# Connectors.net
KiCad netlist of a schematic drawn in Altium Designer
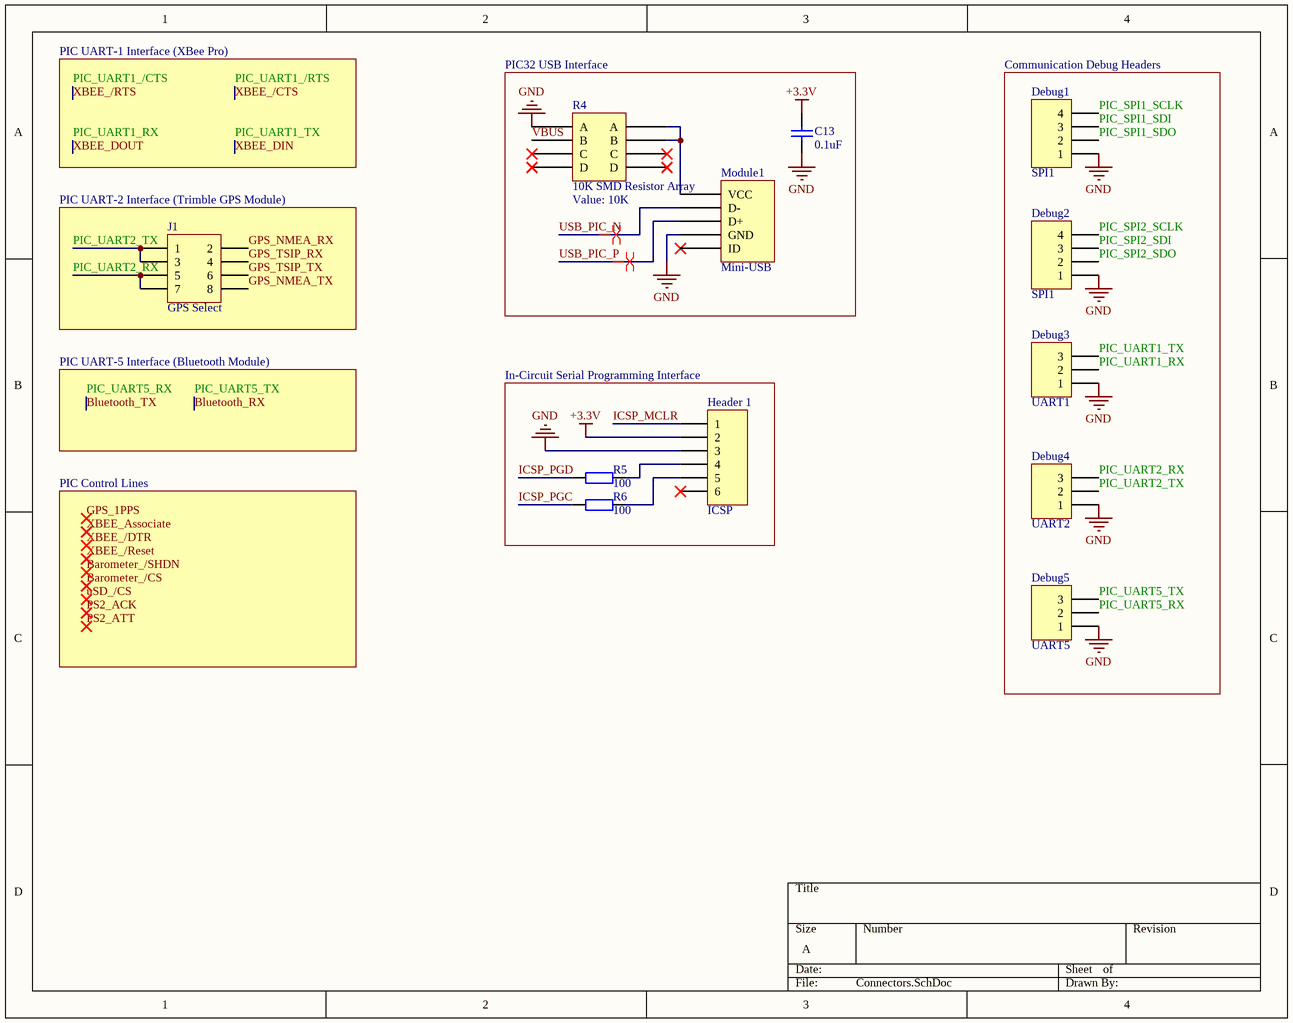
[diagram p0: Connectors.SchDoc]

(export (version "E")
  (design (tool "Eeschema 10.0.6"))
  (components
    (comp (ref "C13")
      (value "0.1uF")
      (footprint "SMD 1206")
      (description "Capacitor")
      (fields (field (name "Comment") "0.1uF SMD 1206"))
      (libsource (lib "Miscellaneous Devices") (part "Cap"))
    )
    (comp (ref "Debug1")
      (value "SPI1")
      (footprint "HDR1X4")
      (description "Header, 4-Pin")
      (fields (field (name "PUBLISHER") "Altium Limited"))
      (libsource (lib "Miscellaneous Connectors") (part "Header 4"))
    )
    (comp (ref "Debug2")
      (value "SPI1")
      (footprint "HDR1X4")
      (description "Header, 4-Pin")
      (fields (field (name "PUBLISHER") "Altium Limited"))
      (libsource (lib "Miscellaneous Connectors") (part "Header 4"))
    )
    (comp (ref "Debug3")
      (value "UART1")
      (footprint "HDR1X3")
      (description "Header, 3-Pin")
      (fields (field (name "PUBLISHER") "Altium Limited"))
      (libsource (lib "Miscellaneous Connectors") (part "Header 3"))
    )
    (comp (ref "Debug4")
      (value "UART2")
      (footprint "HDR1X3")
      (description "Header, 3-Pin")
      (fields (field (name "PUBLISHER") "Altium Limited"))
      (libsource (lib "Miscellaneous Connectors") (part "Header 3"))
    )
    (comp (ref "Debug5")
      (value "UART5")
      (footprint "HDR1X3")
      (description "Header, 3-Pin")
      (fields (field (name "PUBLISHER") "Altium Limited"))
      (libsource (lib "Miscellaneous Connectors") (part "Header 3"))
    )
    (comp (ref "Header 1")
      (value "ICSP")
      (footprint "HDR1X6H")
      (description "Header, 6-Pin")
      (fields (field (name "PUBLISHER") "Altium Limited"))
      (libsource (lib "Miscellaneous Connectors") (part "Header 6"))
    )
    (comp (ref "J1")
      (value "GPS Select")
      (footprint "HDR2X4")
      (description "Header, 4-Pin, Dual row")
      (fields (field (name "PUBLISHER") "Altium Limited"))
      (libsource (lib "Miscellaneous Connectors") (part "Header 4X2"))
    )
    (comp (ref "Module1")
      (value "Mini-USB")
      (footprint "Mini B USB Connector")
      (libsource (lib "Ad-Flier_Parts") (part "Mini USB Connector"))
    )
    (comp (ref "R4")
      (value "10K SMD Resistor Array")
      (footprint "Resistor Array YC164")
      (description "4-Count Resistor Array")
      (fields (field (name "ALTIUM_VALUE") "10K"))
      (libsource (lib "Ad-Flier_Parts") (part "SMD Resistor Array"))
    )
    (comp (ref "R5")
      (value "100")
      (footprint "SMD 0805")
      (description "Resistor")
      (fields (field (name "Comment") "100 SMD 0805"))
      (libsource (lib "Miscellaneous Devices") (part "Res2"))
    )
    (comp (ref "R6")
      (value "100")
      (footprint "SMD 0805")
      (description "Resistor")
      (fields (field (name "Comment") "100 SMD 0805"))
      (libsource (lib "Miscellaneous Devices") (part "Res2"))
    )
  )
  (nets
    (net (code "1") (name "+3.3V") (class "Default")
      (node (ref "C13") (pin "2") (pinfunction "2_2") (pintype "passive"))
      (node (ref "Header 1") (pin "2") (pinfunction "2_2") (pintype "passive"))
    )
    (net (code "4") (name "/Bluetooth_RX") (class "Default")
      (node (ref "Debug5") (pin "3") (pinfunction "3_3") (pintype "passive"))
    )
    (net (code "5") (name "/Bluetooth_TX") (class "Default")
      (node (ref "Debug5") (pin "2") (pinfunction "2_2") (pintype "passive"))
    )
    (net (code "7") (name "/GPS_NMEA_RX") (class "Default")
      (node (ref "J1") (pin "2") (pinfunction "2_2") (pintype "passive"))
    )
    (net (code "8") (name "/GPS_NMEA_TX") (class "Default")
      (node (ref "J1") (pin "8") (pinfunction "8_8") (pintype "passive"))
    )
    (net (code "9") (name "/GPS_TSIP_RX") (class "Default")
      (node (ref "J1") (pin "4") (pinfunction "4_4") (pintype "passive"))
    )
    (net (code "10") (name "/GPS_TSIP_TX") (class "Default")
      (node (ref "J1") (pin "6") (pinfunction "6_6") (pintype "passive"))
    )
    (net (code "11") (name "/ICSP_MCLR") (class "Default")
      (node (ref "Header 1") (pin "1") (pinfunction "1_1") (pintype "passive"))
    )
    (net (code "12") (name "/ICSP_PGC") (class "Default")
      (node (ref "R6") (pin "2") (pinfunction "2_2") (pintype "passive"))
    )
    (net (code "13") (name "/ICSP_PGD") (class "Default")
      (node (ref "R5") (pin "2") (pinfunction "2_2") (pintype "passive"))
    )
    (net (code "14") (name "/PIC_SPI1_SCLK") (class "Default")
      (node (ref "Debug1") (pin "4") (pinfunction "4_4") (pintype "passive"))
    )
    (net (code "15") (name "/PIC_SPI1_SDI") (class "Default")
      (node (ref "Debug1") (pin "3") (pinfunction "3_3") (pintype "passive"))
    )
    (net (code "16") (name "/PIC_SPI1_SDO") (class "Default")
      (node (ref "Debug1") (pin "2") (pinfunction "2_2") (pintype "passive"))
    )
    (net (code "17") (name "/PIC_SPI2_SCLK") (class "Default")
      (node (ref "Debug2") (pin "4") (pinfunction "4_4") (pintype "passive"))
    )
    (net (code "18") (name "/PIC_SPI2_SDI") (class "Default")
      (node (ref "Debug2") (pin "3") (pinfunction "3_3") (pintype "passive"))
    )
    (net (code "19") (name "/PIC_SPI2_SDO") (class "Default")
      (node (ref "Debug2") (pin "2") (pinfunction "2_2") (pintype "passive"))
    )
    (net (code "20") (name "/PIC_UART1_RX") (class "Default")
      (node (ref "Debug3") (pin "2") (pinfunction "2_2") (pintype "passive"))
    )
    (net (code "21") (name "/PIC_UART1_TX") (class "Default")
      (node (ref "Debug3") (pin "3") (pinfunction "3_3") (pintype "passive"))
    )
    (net (code "24") (name "/PIC_UART2_RX") (class "Default")
      (node (ref "Debug4") (pin "3") (pinfunction "3_3") (pintype "passive"))
      (node (ref "J1") (pin "5") (pinfunction "5_5") (pintype "passive"))
      (node (ref "J1") (pin "7") (pinfunction "7_7") (pintype "passive"))
    )
    (net (code "25") (name "/PIC_UART2_TX") (class "Default")
      (node (ref "Debug4") (pin "2") (pinfunction "2_2") (pintype "passive"))
      (node (ref "J1") (pin "1") (pinfunction "1_1") (pintype "passive"))
      (node (ref "J1") (pin "3") (pinfunction "3_3") (pintype "passive"))
    )
    (net (code "28") (name "/USB_PIC_N") (class "Default")
      (node (ref "Module1") (pin "3") (pinfunction "D-_3") (pintype "passive"))
    )
    (net (code "29") (name "/USB_PIC_P") (class "Default")
      (node (ref "Module1") (pin "2") (pinfunction "D+_2") (pintype "passive"))
    )
    (net (code "30") (name "/VBUS") (class "Default")
      (node (ref "R4") (pin "6") (pinfunction "B_6") (pintype "passive"))
    )
    (net (code "35") (name "GND") (class "Default")
      (node (ref "C13") (pin "1") (pinfunction "1_1") (pintype "passive"))
      (node (ref "Debug1") (pin "1") (pinfunction "1_1") (pintype "passive"))
      (node (ref "Debug2") (pin "1") (pinfunction "1_1") (pintype "passive"))
      (node (ref "Debug3") (pin "1") (pinfunction "1_1") (pintype "passive"))
      (node (ref "Debug4") (pin "1") (pinfunction "1_1") (pintype "passive"))
      (node (ref "Debug5") (pin "1") (pinfunction "1_1") (pintype "passive"))
      (node (ref "Header 1") (pin "3") (pinfunction "3_3") (pintype "passive"))
      (node (ref "Module1") (pin "0") (pinfunction "GND_0") (pintype "passive"))
      (node (ref "R4") (pin "5") (pinfunction "A_5") (pintype "passive"))
    )
    (net (code "36") (name "Net-(Header 1-Pad4)") (class "Default")
      (node (ref "Header 1") (pin "4") (pinfunction "4_4") (pintype "passive"))
      (node (ref "R5") (pin "1") (pinfunction "1_1") (pintype "passive"))
    )
    (net (code "37") (name "Net-(Header 1-Pad5)") (class "Default")
      (node (ref "Header 1") (pin "5") (pinfunction "5_5") (pintype "passive"))
      (node (ref "R6") (pin "1") (pinfunction "1_1") (pintype "passive"))
    )
    (net (code "38") (name "Net-(Module1-VCC)") (class "Default")
      (node (ref "Module1") (pin "4") (pinfunction "VCC_4") (pintype "passive"))
      (node (ref "R4") (pin "1") (pinfunction "A_1") (pintype "passive"))
      (node (ref "R4") (pin "2") (pinfunction "B_2") (pintype "passive"))
    )
    (net (code "39") (name "unconnected-(Header 1-Pad6)") (class "Default")
      (node (ref "Header 1") (pin "6") (pinfunction "6_6") (pintype "passive+no_connect"))
    )
    (net (code "40") (name "unconnected-(Module1-ID-Pad1)") (class "Default")
      (node (ref "Module1") (pin "1") (pinfunction "ID_1") (pintype "passive+no_connect"))
    )
    (net (code "41") (name "unconnected-(R4-C-Pad3)") (class "Default")
      (node (ref "R4") (pin "3") (pinfunction "C_3") (pintype "passive+no_connect"))
    )
    (net (code "42") (name "unconnected-(R4-C-Pad7)") (class "Default")
      (node (ref "R4") (pin "7") (pinfunction "C_7") (pintype "passive+no_connect"))
    )
    (net (code "43") (name "unconnected-(R4-D-Pad4)") (class "Default")
      (node (ref "R4") (pin "4") (pinfunction "D_4") (pintype "passive+no_connect"))
    )
    (net (code "44") (name "unconnected-(R4-D-Pad8)") (class "Default")
      (node (ref "R4") (pin "8") (pinfunction "D_8") (pintype "passive+no_connect"))
    )
  )
)
